# Single_Stage.net
KiCad netlist of a schematic drawn in Altium Designer
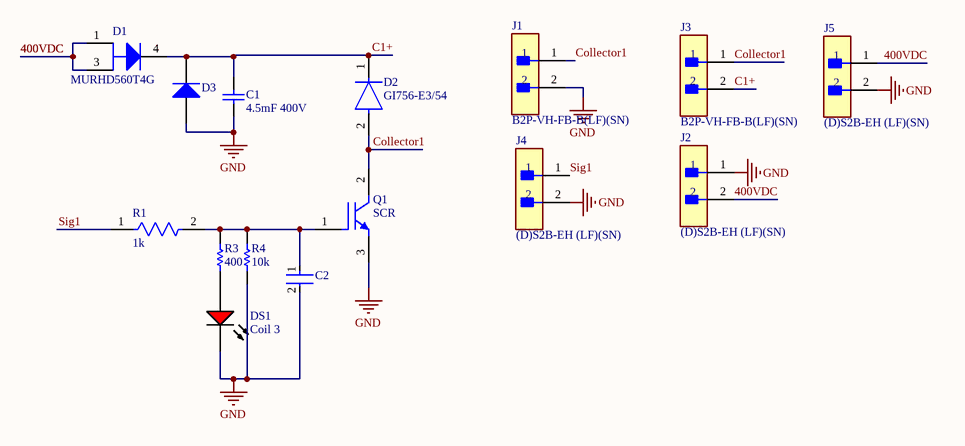
[diagram p0: Single_Stage.SchDoc]

(export (version "E")
  (design (tool "Eeschema 10.0.6"))
  (components
    (comp (ref "C1")
      (value "4.5mF 400V")
      (description "Capacitor")
      (fields (field (name "Comment") "asas"))
      (libsource (lib "Simulation Generic Components") (part "Capacitor"))
    )
    (comp (ref "C2")
      (value "CGA3E2X7R1H104K080AA")
      (footprint "FP-CGA3E-0_3-0_1-IPC_A")
      (description "Cap Ceramic 100nF 50V X7R 10% Pad SMD 0603 +125°C Automotive T/R")
      (fields (field (name "TOLERANCE") "10%") (field (name "VOLTAGE") "50V"))
      (libsource (lib "Altium Content Vault") (part "b4654b650e69147ec39a6b967a45e02"))
    )
    (comp (ref "D1")
      (value "MURHD560T4G")
      (footprint "ONSC-DPAK-3-369C-01_V")
      (description "Power Rectifier, 3-Pin DPAK, Pb-Free, Tape and Reel")
      (fields (field (name "MANUFACTURER") "On Semiconductor"))
      (libsource (lib "Altium Content Vault") (part "ONSC-D-A1A3K4-3"))
    )
    (comp (ref "D2")
      (value "GI756-E3/54")
      (footprint "FP-P600-MFG")
      (description "DIODE GEN PURP 600V 6A P600")
      (fields (field (name "VOLTAGE") "1.2kV"))
      (libsource (lib "Altium Content Vault") (part "d7152d700b627762746794eb795d46e"))
    )
    (comp (ref "D3")
      (value "R")
      (footprint "DIOD-S1M-13-F-SMA-2_V")
      (fields (field (name "MANUFACTURER") "Diodes Inc") (field (name "PARTNUMBER") "S1M-13-F"))
      (libsource (lib "Altium Content Vault") (part "DIOD-D-A1K2-2"))
    )
    (comp (ref "DS1")
      (value "Coil 3")
      (footprint "VISH-TLMX1100_V")
      (description "LED, RED, 2.1 V, -40 to 100 degC, 2-Pin SMD (0603), RoHS, Tape and Reel")
      (fields (field (name "TOLERANCE") "5%"))
      (libsource (lib "Altium Content Vault") (part "LED-RED-AK-2"))
    )
    (comp (ref "J1")
      (value "B2P-VH-FB-B(LF)(SN)")
      (footprint "FP-B2P-VH-FB-B_LF_SN-MFG")
      (description "CONN HEADER VERT 2POS 3.96MM")
      (libsource (lib "Altium Content Vault") (part "3bc925449376181038e59eaffc5286c"))
    )
    (comp (ref "J2")
      (value "(D)S2B-EH (LF)(SN)")
      (footprint "FP-D_S2B-EH_LF_SN-MFG")
      (description "CONN HEADER R/A 2POS 2.5MM")
      (libsource (lib "Altium Content Vault") (part "3bc925449376181038e59eaffc5286c"))
    )
    (comp (ref "J3")
      (value "B2P-VH-FB-B(LF)(SN)")
      (footprint "FP-B2P-VH-FB-B_LF_SN-MFG")
      (description "CONN HEADER VERT 2POS 3.96MM")
      (libsource (lib "Altium Content Vault") (part "3bc925449376181038e59eaffc5286c"))
    )
    (comp (ref "J4")
      (value "(D)S2B-EH (LF)(SN)")
      (footprint "FP-D_S2B-EH_LF_SN-MFG")
      (description "CONN HEADER R/A 2POS 2.5MM")
      (libsource (lib "Altium Content Vault") (part "3bc925449376181038e59eaffc5286c"))
    )
    (comp (ref "J5")
      (value "(D)S2B-EH (LF)(SN)")
      (footprint "FP-D_S2B-EH_LF_SN-MFG")
      (description "CONN HEADER R/A 2POS 2.5MM")
      (libsource (lib "Altium Content Vault") (part "3bc925449376181038e59eaffc5286c"))
    )
    (comp (ref "Q1")
      (value "SCR")
      (footprint "INF-PG-TO247-3-44_A")
      (description "High Speed IGBT in NPT-Technology, PG-TO247-3-44, Tube, Green")
      (fields (field (name "PARTNUMBER") "SGW30N60HS") (field (name "MANUFACTURER") "Infineon"))
      (libsource (lib "Altium Content Vault") (part "INF-IGBT-N-GEC-3_A"))
    )
    (comp (ref "R1")
      (value "1k")
      (footprint "FP-CRCW2512-e3-MFG")
      (description "RES Thick Film, 100kΩ, 1%, 1W, 100ppm/°C, 2512")
      (fields (field (name "TOLERANCE") "1%"))
      (libsource (lib "Altium Content Vault") (part "1029c3af85768c4190bb7ad29bc67b5"))
    )
    (comp (ref "R3")
      (value "400")
      (footprint "RESC1609X50X30NL8T20")
      (description "Chip Resistor, 10 KOhm, +/- 1%, 100 mW, -55 to 155 degC, 0603 (1608 Metric), RoHS, Tape and Reel")
      (fields (field (name "MANUFACTURER") "Vishay Semiconductor"))
      (libsource (lib "Altium Content Vault") (part "RES-2"))
    )
    (comp (ref "R4")
      (value "10k")
      (footprint "RESC1609X50X30NL8T20")
      (description "Chip Resistor, 10 KOhm, +/- 1%, 100 mW, -55 to 155 degC, 0603 (1608 Metric), RoHS, Tape and Reel")
      (fields (field (name "MANUFACTURER") "Vishay Semiconductor"))
      (libsource (lib "Altium Content Vault") (part "RES-2"))
    )
  )
  (nets
    (net (code "1") (name "/400VDC") (class "Default")
      (node (ref "D1") (pin "1") (pinfunction "A_1") (pintype "passive"))
      (node (ref "D1") (pin "3") (pinfunction "A_3") (pintype "passive"))
      (node (ref "J2") (pin "2") (pinfunction "2_2") (pintype "passive"))
      (node (ref "J5") (pin "1") (pinfunction "1_1") (pintype "passive"))
    )
    (net (code "2") (name "/C1+") (class "Default")
      (node (ref "C1") (pin "2") (pinfunction "2_2") (pintype "passive"))
      (node (ref "D1") (pin "4") (pinfunction "K_4") (pintype "passive"))
      (node (ref "D2") (pin "1") (pinfunction "C_1") (pintype "passive"))
      (node (ref "D3") (pin "2") (pinfunction "K_2") (pintype "passive"))
      (node (ref "J3") (pin "2") (pinfunction "2_2") (pintype "passive"))
    )
    (net (code "3") (name "/Collector1") (class "Default")
      (node (ref "D2") (pin "2") (pinfunction "A_2") (pintype "passive"))
      (node (ref "J1") (pin "1") (pinfunction "1_1") (pintype "passive"))
      (node (ref "J3") (pin "1") (pinfunction "1_1") (pintype "passive"))
      (node (ref "Q1") (pin "2") (pinfunction "C_2") (pintype "passive"))
    )
    (net (code "4") (name "/Sig1") (class "Default")
      (node (ref "J4") (pin "1") (pinfunction "1_1") (pintype "passive"))
      (node (ref "R1") (pin "1") (pinfunction "1_1") (pintype "passive"))
    )
    (net (code "5") (name "GND") (class "Default")
      (node (ref "C1") (pin "1") (pinfunction "1_1") (pintype "passive"))
      (node (ref "C2") (pin "2") (pinfunction "2_2") (pintype "passive"))
      (node (ref "D3") (pin "1") (pinfunction "A_1") (pintype "passive"))
      (node (ref "DS1") (pin "2") (pinfunction "K_2") (pintype "passive"))
      (node (ref "J1") (pin "2") (pinfunction "2_2") (pintype "passive"))
      (node (ref "J2") (pin "1") (pinfunction "1_1") (pintype "passive"))
      (node (ref "J4") (pin "2") (pinfunction "2_2") (pintype "passive"))
      (node (ref "J5") (pin "2") (pinfunction "2_2") (pintype "passive"))
      (node (ref "Q1") (pin "3") (pinfunction "E_3") (pintype "passive"))
      (node (ref "R4") (pin "1") (pinfunction "1_1") (pintype "passive"))
    )
    (net (code "6") (name "Net-(DS1-A)") (class "Default")
      (node (ref "DS1") (pin "1") (pinfunction "A_1") (pintype "passive"))
      (node (ref "R3") (pin "1") (pinfunction "1_1") (pintype "passive"))
    )
    (net (code "7") (name "Net-(Q1-G)") (class "Default")
      (node (ref "C2") (pin "1") (pinfunction "1_1") (pintype "passive"))
      (node (ref "Q1") (pin "1") (pinfunction "G_1") (pintype "passive"))
      (node (ref "R1") (pin "2") (pinfunction "2_2") (pintype "passive"))
      (node (ref "R3") (pin "2") (pinfunction "2_2") (pintype "passive"))
      (node (ref "R4") (pin "2") (pinfunction "2_2") (pintype "passive"))
    )
  )
)
